# QPL9058.net
KiCad netlist of a schematic drawn in Altium Designer
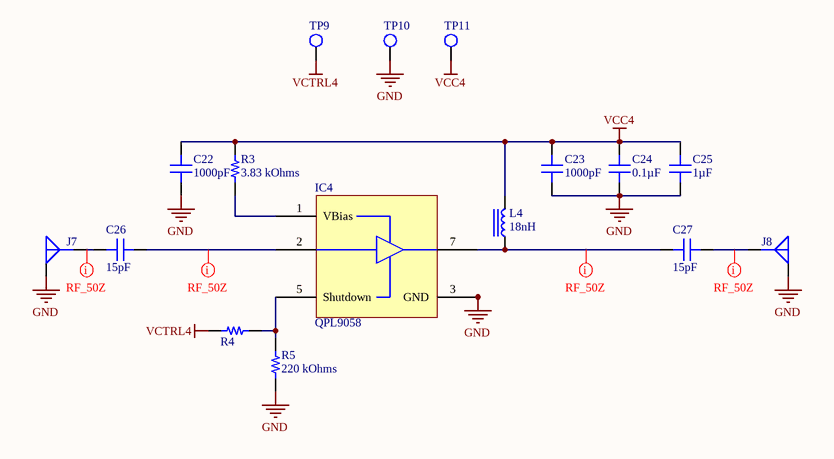
[diagram p0: QPL9058.SchDoc]

(export (version "E")
  (design (tool "Eeschema 10.0.6"))
  (components
    (comp (ref "C22")
      (value "1000pF")
      (footprint "CAP 0402_1005")
      (description "CAP CER 1000PF 50V X7R 0402")
      (fields
        (field (name "PART NUMBER") "GCM155R71H102KA37D")
        (field (name "MANUFACTURER") "Murata Electronics")
      )
      (libsource (lib "Celestial Altium Library - altium_library") (part "Capacitor"))
    )
    (comp (ref "C23")
      (value "1000pF")
      (footprint "CAP 0402_1005")
      (description "CAP CER 1000PF 50V X7R 0402")
      (fields
        (field (name "PART NUMBER") "GCM155R71H102KA37D")
        (field (name "MANUFACTURER") "Murata Electronics")
      )
      (libsource (lib "Celestial Altium Library - altium_library") (part "Capacitor"))
    )
    (comp (ref "C24")
      (value "0.1µF")
      (footprint "CAP 0402_1005")
      (description "CAP CER 0.1UF 16V X7R 0402")
      (fields (field (name "PART NUMBER") "EMK105B7104KV-F") (field (name "MANUFACTURER") "Taiyo Yuden"))
      (libsource (lib "Celestial Altium Library - altium_library") (part "Capacitor"))
    )
    (comp (ref "C25")
      (value "1µF")
      (footprint "CAP 0402_1005")
      (description "CAP CER 1UF 10V X5R 0402")
      (fields
        (field (name "PART NUMBER") "CL05A105KP5NNNC")
        (field (name "MANUFACTURER") "Samsung Electro-Mechanics")
      )
      (libsource (lib "Celestial Altium Library - altium_library") (part "Capacitor"))
    )
    (comp (ref "C26")
      (value "15pF")
      (footprint "CAP 0402_1005 RF")
      (description "CAP CER 15PF 50V C0G/NP0 0402")
      (fields
        (field (name "PART NUMBER") "GJM1555C1H150JB01D")
        (field (name "MANUFACTURER") "Murata Electronics")
      )
      (libsource (lib "Celestial Altium Library - altium_library") (part "Capacitor"))
    )
    (comp (ref "C27")
      (value "15pF")
      (footprint "CAP 0402_1005 RF")
      (description "CAP CER 15PF 50V C0G/NP0 0402")
      (fields
        (field (name "PART NUMBER") "GJM1555C1H150JB01D")
        (field (name "MANUFACTURER") "Murata Electronics")
      )
      (libsource (lib "Celestial Altium Library - altium_library") (part "Capacitor"))
    )
    (comp (ref "IC4")
      (value "QPL9058")
      (footprint "Qorvo LNA DFN-8 2X2")
      (description "0.5 – 6.0 GHz Ultra Low-Noise LNA")
      (libsource (lib "IC") (part "QPL9058"))
    )
    (comp (ref "J7")
      (value "CON-SMA-EDGE-S")
      (footprint "CON-SMA-EDGE-S")
      (description "CONN SMA JACK STR EDGE MNT")
      (libsource (lib "Connector") (part "CON-SMA-EDGE-S"))
    )
    (comp (ref "J8")
      (value "CON-SMA-EDGE-S")
      (footprint "CON-SMA-EDGE-S")
      (description "CONN SMA JACK STR EDGE MNT")
      (libsource (lib "Connector") (part "CON-SMA-EDGE-S"))
    )
    (comp (ref "L4")
      (value "18nH")
      (footprint "0603CS")
      (description "Fixed Inductors 1608 18nH Unshld 5% 700mA 170mOhms AECQ2")
      (libsource (lib "Inductor") (part "0603CS-18NXJLW"))
    )
    (comp (ref "R3")
      (value "3.83 kOhms")
      (footprint "RES 0402_1005")
      (description "RES SMD 3.83K OHM 1% 1/16W 0402")
      (fields (field (name "PART NUMBER") "RC0402FR-073K83L") (field (name "MANUFACTURER") "Yageo"))
      (libsource (lib "Celestial Altium Library - altium_library") (part "Resistor"))
    )
    (comp (ref "R4")
      (value "~")
      (footprint "RES 0402_1005")
      (description "RES SMD 0 OHM JUMPER 1/16W 0402")
      (fields (field (name "PART NUMBER") "RC0402JR-070RP") (field (name "MANUFACTURER") "Yageo"))
      (libsource (lib "Celestial Altium Library - altium_library") (part "Resistor"))
    )
    (comp (ref "R5")
      (value "220 kOhms")
      (footprint "RES 0402_1005")
      (description "RES SMD 220K OHM 1% 1/16W 0402")
      (fields (field (name "PART NUMBER") "RC0402FR-07220KL") (field (name "MANUFACTURER") "Yageo"))
      (libsource (lib "Celestial Altium Library - altium_library") (part "Resistor"))
    )
    (comp (ref "TP9")
      (value "Test Point-THM")
      (footprint "KEYSTONE-THM-TestPoint")
      (description "THRU HOLE MOUNT TEST POINTS")
      (libsource (lib "Misc") (part "Test Point-THM"))
    )
    (comp (ref "TP10")
      (value "Test Point-THM")
      (footprint "KEYSTONE-THM-TestPoint")
      (description "THRU HOLE MOUNT TEST POINTS")
      (libsource (lib "Misc") (part "Test Point-THM"))
    )
    (comp (ref "TP11")
      (value "Test Point-THM")
      (footprint "KEYSTONE-THM-TestPoint")
      (description "THRU HOLE MOUNT TEST POINTS")
      (libsource (lib "Misc") (part "Test Point-THM"))
    )
  )
  (nets
    (net (code "1") (name "GND") (class "Default")
      (node (ref "C22") (pin "2") (pinfunction "2_2") (pintype "passive"))
      (node (ref "C23") (pin "1") (pinfunction "1_1") (pintype "passive"))
      (node (ref "C24") (pin "1") (pinfunction "1_1") (pintype "passive"))
      (node (ref "C25") (pin "1") (pinfunction "1_1") (pintype "passive"))
      (node (ref "IC4") (pin "3") (pinfunction "GND_3") (pintype "passive"))
      (node (ref "IC4") (pin "4") (pinfunction "GND_4") (pintype "passive"))
      (node (ref "IC4") (pin "6") (pinfunction "GND_6") (pintype "passive"))
      (node (ref "IC4") (pin "8") (pinfunction "GND_8") (pintype "passive"))
      (node (ref "IC4") (pin "9") (pinfunction "GND_9") (pintype "passive"))
      (node (ref "J7") (pin "2") (pinfunction "G_2") (pintype "passive"))
      (node (ref "J8") (pin "2") (pinfunction "G_2") (pintype "passive"))
      (node (ref "R5") (pin "1") (pinfunction "1_1") (pintype "passive"))
      (node (ref "TP10") (pin "1") (pinfunction "TP_1") (pintype "passive"))
    )
    (net (code "2") (name "Net-(IC4-IN)") (class "Default")
      (node (ref "C26") (pin "2") (pinfunction "2_2") (pintype "passive"))
      (node (ref "IC4") (pin "2") (pinfunction "IN_2") (pintype "passive"))
    )
    (net (code "3") (name "Net-(IC4-OUT)") (class "Default")
      (node (ref "C27") (pin "1") (pinfunction "1_1") (pintype "passive"))
      (node (ref "IC4") (pin "7") (pinfunction "OUT_7") (pintype "passive"))
      (node (ref "L4") (pin "1") (pinfunction "1_1") (pintype "passive"))
    )
    (net (code "4") (name "Net-(IC4-Shutdown)") (class "Default")
      (node (ref "IC4") (pin "5") (pinfunction "Shutdown_5") (pintype "passive"))
      (node (ref "R4") (pin "2") (pinfunction "2_2") (pintype "passive"))
      (node (ref "R5") (pin "2") (pinfunction "2_2") (pintype "passive"))
    )
    (net (code "5") (name "Net-(IC4-VBias)") (class "Default")
      (node (ref "IC4") (pin "1") (pinfunction "VBias_1") (pintype "passive"))
      (node (ref "R3") (pin "1") (pinfunction "1_1") (pintype "passive"))
    )
    (net (code "6") (name "Net-(J7-S)") (class "Default")
      (node (ref "C26") (pin "1") (pinfunction "1_1") (pintype "passive"))
      (node (ref "J7") (pin "1") (pinfunction "S_1") (pintype "passive"))
    )
    (net (code "7") (name "Net-(J8-S)") (class "Default")
      (node (ref "C27") (pin "2") (pinfunction "2_2") (pintype "passive"))
      (node (ref "J8") (pin "1") (pinfunction "S_1") (pintype "passive"))
    )
    (net (code "8") (name "VCC4") (class "Default")
      (node (ref "C22") (pin "1") (pinfunction "1_1") (pintype "passive"))
      (node (ref "C23") (pin "2") (pinfunction "2_2") (pintype "passive"))
      (node (ref "C24") (pin "2") (pinfunction "2_2") (pintype "passive"))
      (node (ref "C25") (pin "2") (pinfunction "2_2") (pintype "passive"))
      (node (ref "L4") (pin "2") (pinfunction "2_2") (pintype "passive"))
      (node (ref "R3") (pin "2") (pinfunction "2_2") (pintype "passive"))
      (node (ref "TP11") (pin "1") (pinfunction "TP_1") (pintype "passive"))
    )
    (net (code "9") (name "VCTRL4") (class "Default")
      (node (ref "R4") (pin "1") (pinfunction "1_1") (pintype "passive"))
      (node (ref "TP9") (pin "1") (pinfunction "TP_1") (pintype "passive"))
    )
  )
)
